# signal_generator.net
KiCad netlist of a schematic drawn in EAGLE
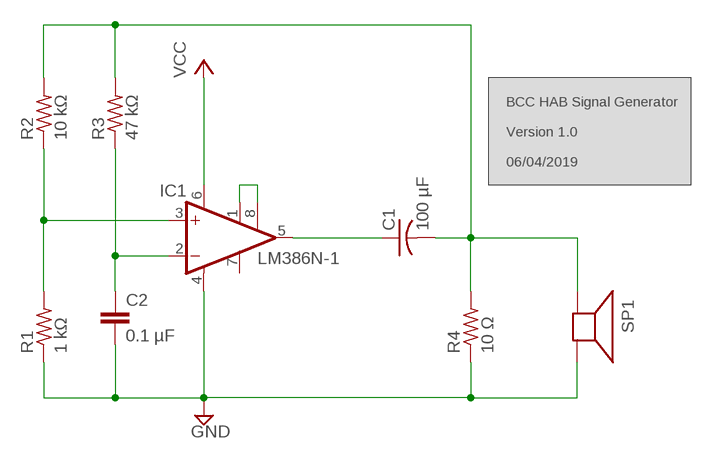
[diagram p0: schematic, sheet 1]

(export (version "E")
  (design (tool "Eeschema 10.0.6"))
  (components
    (comp (ref "C1")
      (value "100 µF")
      (footprint "eagle-import:C025-024X044")
      (libsource (lib "eagle-import") (part "C-US025-024X044"))
    )
    (comp (ref "C2")
      (value "0.1 µF")
      (footprint "eagle-import:C2.5-3")
      (libsource (lib "eagle-import") (part "C2,5-3"))
    )
    (comp (ref "IC1")
      (value "LM386N-1")
      (footprint "eagle-import:DIL08")
      (libsource (lib "eagle-import") (part "LM386?-N1"))
    )
    (comp (ref "R1")
      (value "1 kΩ")
      (footprint "eagle-import:0204_7")
      (libsource (lib "eagle-import") (part "R-US_0204/7"))
    )
    (comp (ref "R2")
      (value "10 kΩ")
      (footprint "eagle-import:0204_7")
      (libsource (lib "eagle-import") (part "R-US_0204/7"))
    )
    (comp (ref "R3")
      (value "47 kΩ")
      (footprint "eagle-import:0204_7")
      (libsource (lib "eagle-import") (part "R-US_0204/7"))
    )
    (comp (ref "R4")
      (value "10 Ω")
      (footprint "eagle-import:0204_7")
      (libsource (lib "eagle-import") (part "R-US_0204/7"))
    )
    (comp (ref "SP1")
      (value "SPEAKER/AL60P")
      (footprint "eagle-import:AL60P")
      (libsource (lib "eagle-import") (part "SPEAKER/AL60P"))
    )
  )
  (nets
    (net (code "1") (name "GND") (class "Default")
      (node (ref "C2") (pin "2") (pinfunction "2_2") (pintype "passive"))
      (node (ref "IC1") (pin "4") (pinfunction "GND_4") (pintype "power_in"))
      (node (ref "R1") (pin "1") (pinfunction "1_1") (pintype "passive"))
      (node (ref "R4") (pin "1") (pinfunction "1_1") (pintype "passive"))
      (node (ref "SP1") (pin "2") (pinfunction "-_2") (pintype "passive"))
    )
    (net (code "2") (name "Net-(IC1-+IN)") (class "Default")
      (node (ref "IC1") (pin "3") (pinfunction "+IN_3") (pintype "input"))
      (node (ref "R1") (pin "2") (pinfunction "2_2") (pintype "passive"))
      (node (ref "R2") (pin "1") (pinfunction "1_1") (pintype "passive"))
    )
    (net (code "3") (name "Net-(IC1--IN)") (class "Default")
      (node (ref "C2") (pin "1") (pinfunction "1_1") (pintype "passive"))
      (node (ref "IC1") (pin "2") (pinfunction "-IN_2") (pintype "input"))
      (node (ref "R3") (pin "1") (pinfunction "1_1") (pintype "passive"))
    )
    (net (code "4") (name "Net-(IC1-GAIN-Pad1)") (class "Default")
      (node (ref "IC1") (pin "1") (pinfunction "GAIN_1") (pintype "passive"))
      (node (ref "IC1") (pin "8") (pinfunction "GAIN_8") (pintype "passive"))
    )
    (net (code "5") (name "Net-(IC1-OUT)") (class "Default")
      (node (ref "C1") (pin "1") (pinfunction "1_1") (pintype "passive"))
      (node (ref "IC1") (pin "5") (pinfunction "OUT_5") (pintype "output"))
    )
    (net (code "6") (name "Net-(SP1-+)") (class "Default")
      (node (ref "C1") (pin "2") (pinfunction "2_2") (pintype "passive"))
      (node (ref "R2") (pin "2") (pinfunction "2_2") (pintype "passive"))
      (node (ref "R3") (pin "2") (pinfunction "2_2") (pintype "passive"))
      (node (ref "R4") (pin "2") (pinfunction "2_2") (pintype "passive"))
      (node (ref "SP1") (pin "1") (pinfunction "+_1") (pintype "passive"))
    )
    (net (code "7") (name "VCC") (class "Default")
      (node (ref "IC1") (pin "6") (pinfunction "VS_6") (pintype "power_in"))
    )
    (net (code "8") (name "unconnected-(IC1-BYPASS-Pad7)") (class "Default")
      (node (ref "IC1") (pin "7") (pinfunction "BYPASS_7") (pintype "passive"))
    )
  )
)
